# RS485_Ethernet_Gateway_v1_0.net
KiCad netlist of a schematic drawn in EAGLE
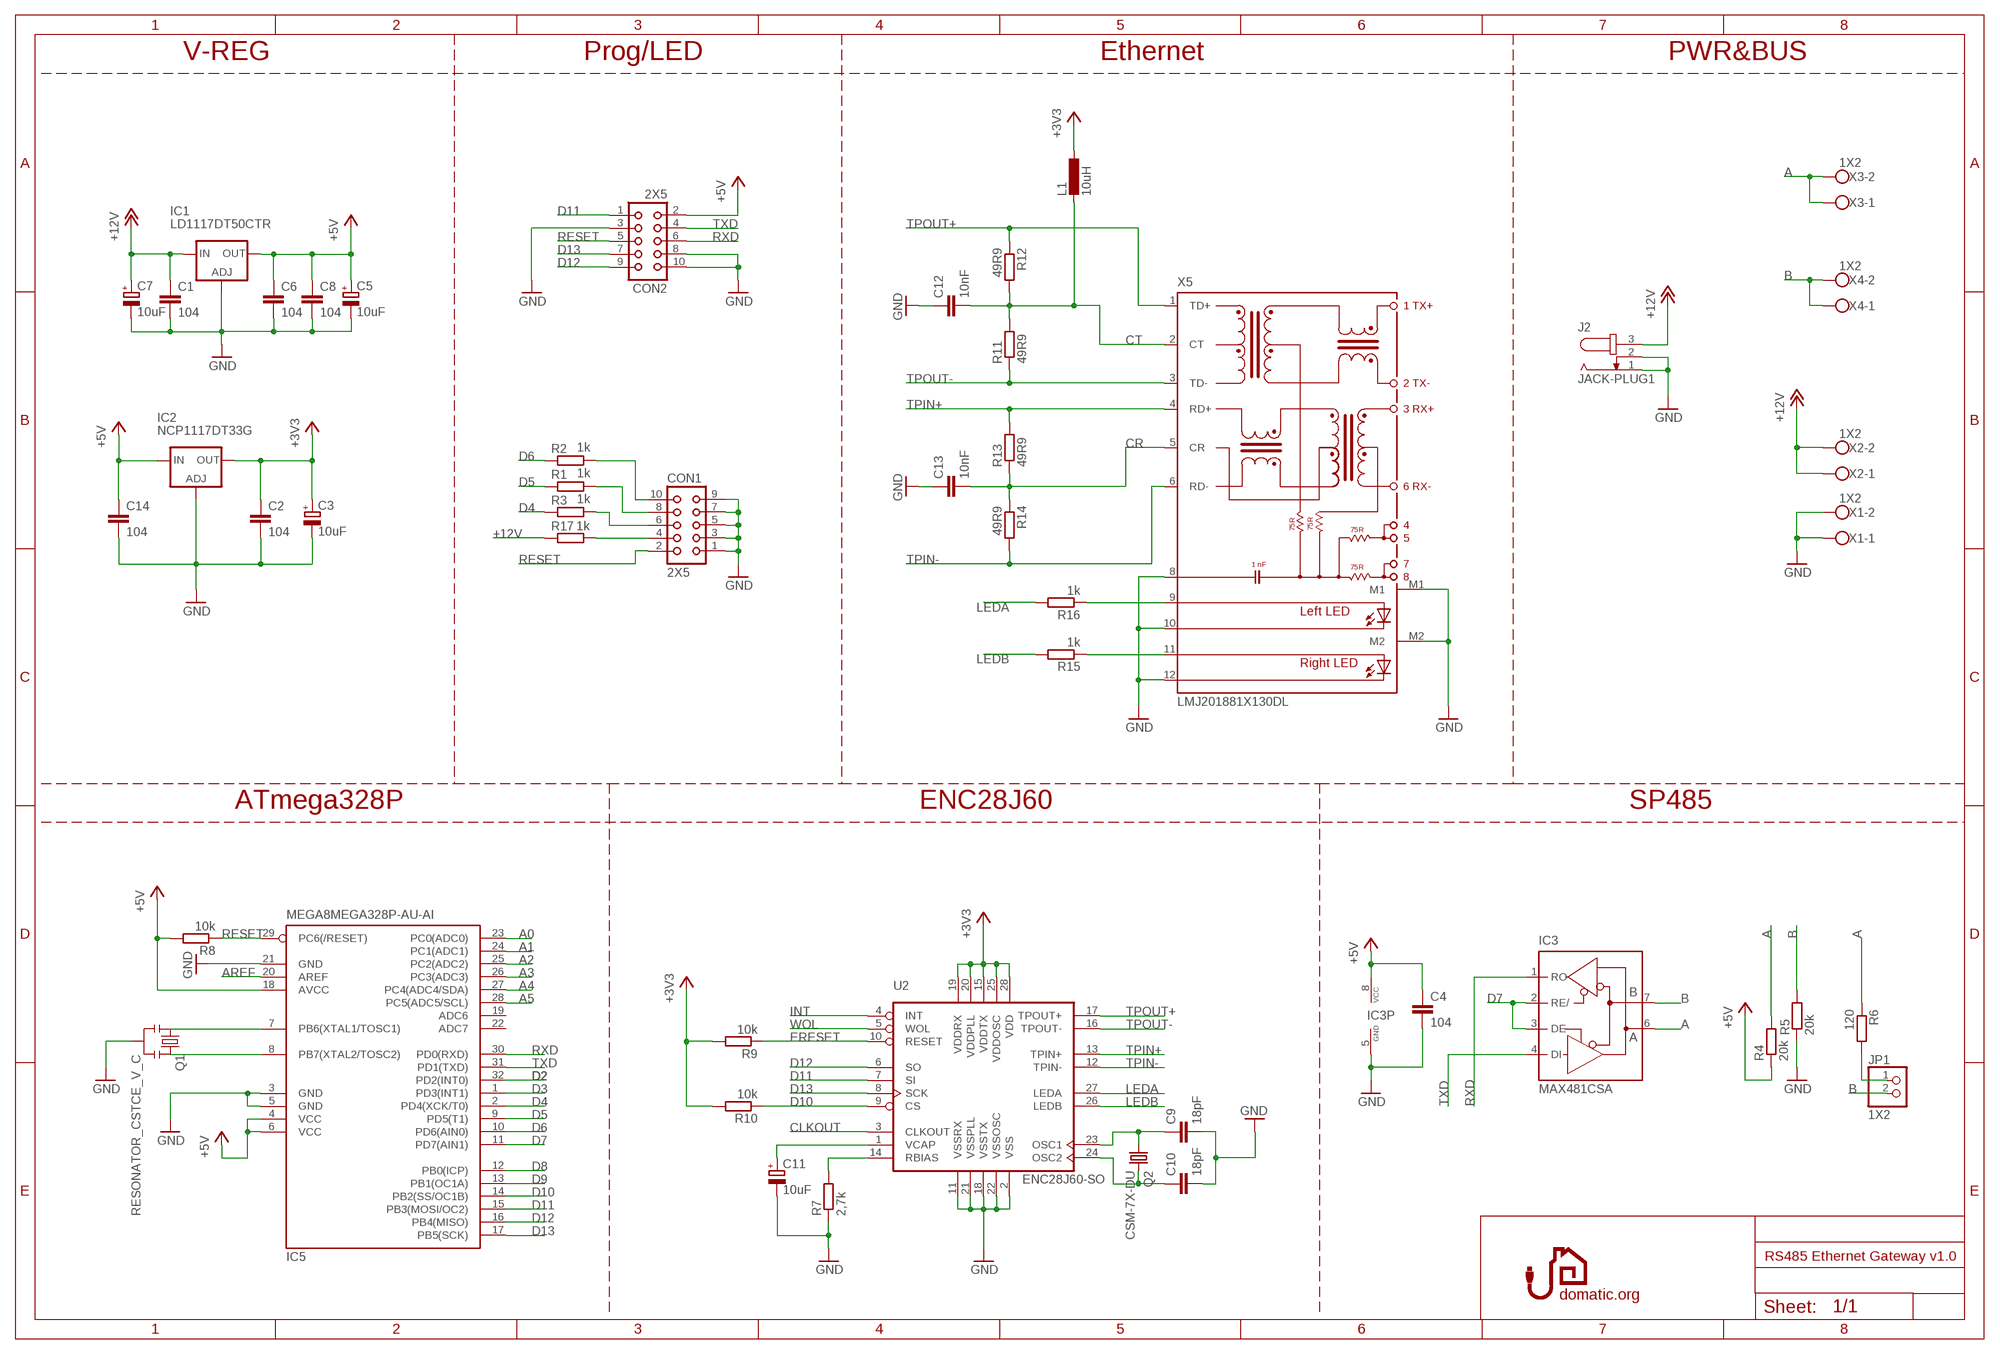
[diagram p0: schematic, sheet 1]

(export (version "E")
  (design (tool "Eeschema 10.0.6"))
  (components
    (comp (ref "C1")
      (value "104")
      (footprint "eagle-import:C0603")
      (libsource (lib "eagle-import") (part "C-EUC0603"))
    )
    (comp (ref "C2")
      (value "104")
      (footprint "eagle-import:C0603")
      (libsource (lib "eagle-import") (part "C-EUC0603"))
    )
    (comp (ref "C3")
      (value "10uF")
      (footprint "eagle-import:E2,5-7")
      (libsource (lib "eagle-import") (part "CPOL-EUE2.5-7"))
    )
    (comp (ref "C4")
      (value "104")
      (footprint "eagle-import:C0603")
      (libsource (lib "eagle-import") (part "C-EUC0603"))
    )
    (comp (ref "C5")
      (value "10uF")
      (footprint "eagle-import:E2,5-7")
      (libsource (lib "eagle-import") (part "CPOL-EUE2.5-7"))
    )
    (comp (ref "C6")
      (value "104")
      (footprint "eagle-import:C0603")
      (libsource (lib "eagle-import") (part "C-EUC0603"))
    )
    (comp (ref "C7")
      (value "10uF")
      (footprint "eagle-import:E2,5-7")
      (libsource (lib "eagle-import") (part "CPOL-EUE2.5-7"))
    )
    (comp (ref "C8")
      (value "104")
      (footprint "eagle-import:C0603")
      (libsource (lib "eagle-import") (part "C-EUC0603"))
    )
    (comp (ref "C9")
      (value "18pF")
      (footprint "eagle-import:C0603")
      (libsource (lib "eagle-import") (part "C-EUC0603"))
    )
    (comp (ref "C10")
      (value "18pF")
      (footprint "eagle-import:C0603")
      (libsource (lib "eagle-import") (part "C-EUC0603"))
    )
    (comp (ref "C11")
      (value "10uF")
      (footprint "eagle-import:E2,5-7")
      (libsource (lib "eagle-import") (part "CPOL-EUE2.5-7"))
    )
    (comp (ref "C12")
      (value "10nF")
      (footprint "eagle-import:C0603")
      (libsource (lib "eagle-import") (part "C-EUC0603"))
    )
    (comp (ref "C13")
      (value "10nF")
      (footprint "eagle-import:C0603")
      (libsource (lib "eagle-import") (part "C-EUC0603"))
    )
    (comp (ref "C14")
      (value "104")
      (footprint "eagle-import:C0603")
      (libsource (lib "eagle-import") (part "C-EUC0603"))
    )
    (comp (ref "CON1")
      (value "2X5")
      (footprint "eagle-import:CON10L")
      (libsource (lib "eagle-import") (part "CON10L"))
    )
    (comp (ref "CON2")
      (value "2X5")
      (footprint "eagle-import:CON10L")
      (libsource (lib "eagle-import") (part "CON10L"))
    )
    (comp (ref "IC1")
      (value "LD1117DT50CTR")
      (footprint "eagle-import:DPACK")
      (libsource (lib "eagle-import") (part "LD117A?DT50TR"))
    )
    (comp (ref "IC2")
      (value "NCP1117DT33G")
      (footprint "eagle-import:DPACK")
      (libsource (lib "eagle-import") (part "LD117A?DT33TR"))
    )
    (comp (ref "IC3")
      (value "MAX481CSA")
      (footprint "eagle-import:SO08")
      (fields (field (name "MF") "MAXIM"))
      (libsource (lib "eagle-import") (part "MAX481CSA"))
    )
    (comp (ref "IC5")
      (value "MEGA8MEGA328P-AU-AI")
      (footprint "eagle-import:TQFP32-08")
      (fields (field (name "MPN") "ATMEGA328P-AU"))
      (libsource (lib "eagle-import") (part "MEGA8-AIMEGA328P-AU"))
    )
    (comp (ref "J2")
      (value "JACK-PLUG1")
      (footprint "eagle-import:SPC4078")
      (libsource (lib "eagle-import") (part "JACK-PLUG1"))
    )
    (comp (ref "JP1")
      (value "1X2")
      (footprint "eagle-import:1X02")
      (libsource (lib "eagle-import") (part "PINHD-1X2"))
    )
    (comp (ref "L1")
      (value "10uH")
      (footprint "eagle-import:C1608")
      (libsource (lib "eagle-import") (part "L-EU0603"))
    )
    (comp (ref "Q1")
      (value "RESONATOR_CSTCE_V_C")
      (footprint "eagle-import:CSTCE_V_C")
      (libsource (lib "eagle-import") (part "RESONATOR_CSTCE_V_C"))
    )
    (comp (ref "Q2")
      (value "CSM-7X-DU")
      (footprint "eagle-import:CSM-7X-DU")
      (libsource (lib "eagle-import") (part "CSM-7X-DU"))
    )
    (comp (ref "R1")
      (value "1k")
      (footprint "eagle-import:R0603")
      (libsource (lib "eagle-import") (part "R-EU_R0603"))
    )
    (comp (ref "R2")
      (value "1k")
      (footprint "eagle-import:R0603")
      (libsource (lib "eagle-import") (part "R-EU_R0603"))
    )
    (comp (ref "R3")
      (value "1k")
      (footprint "eagle-import:R0603")
      (libsource (lib "eagle-import") (part "R-EU_R0603"))
    )
    (comp (ref "R4")
      (value "20k")
      (footprint "eagle-import:R0603")
      (libsource (lib "eagle-import") (part "R-EU_R0603"))
    )
    (comp (ref "R5")
      (value "20k")
      (footprint "eagle-import:R0603")
      (libsource (lib "eagle-import") (part "R-EU_R0603"))
    )
    (comp (ref "R6")
      (value "120")
      (footprint "eagle-import:R0603")
      (libsource (lib "eagle-import") (part "R-EU_R0603"))
    )
    (comp (ref "R7")
      (value "2,7k")
      (footprint "eagle-import:R0603")
      (libsource (lib "eagle-import") (part "R-EU_R0603"))
    )
    (comp (ref "R8")
      (value "10k")
      (footprint "eagle-import:R0603")
      (libsource (lib "eagle-import") (part "R-EU_R0603"))
    )
    (comp (ref "R9")
      (value "10k")
      (footprint "eagle-import:R0603")
      (libsource (lib "eagle-import") (part "R-EU_R0603"))
    )
    (comp (ref "R10")
      (value "10k")
      (footprint "eagle-import:R0603")
      (libsource (lib "eagle-import") (part "R-EU_R0603"))
    )
    (comp (ref "R11")
      (value "49R9")
      (footprint "eagle-import:R0603")
      (libsource (lib "eagle-import") (part "R-EU_R0603"))
    )
    (comp (ref "R12")
      (value "49R9")
      (footprint "eagle-import:R0603")
      (libsource (lib "eagle-import") (part "R-EU_R0603"))
    )
    (comp (ref "R13")
      (value "49R9")
      (footprint "eagle-import:R0603")
      (libsource (lib "eagle-import") (part "R-EU_R0603"))
    )
    (comp (ref "R14")
      (value "49R9")
      (footprint "eagle-import:R0603")
      (libsource (lib "eagle-import") (part "R-EU_R0603"))
    )
    (comp (ref "R15")
      (value "1k")
      (footprint "eagle-import:R0603")
      (libsource (lib "eagle-import") (part "R-EU_R0603"))
    )
    (comp (ref "R16")
      (value "1k")
      (footprint "eagle-import:R0603")
      (libsource (lib "eagle-import") (part "R-EU_R0603"))
    )
    (comp (ref "R17")
      (value "1k")
      (footprint "eagle-import:R0603")
      (libsource (lib "eagle-import") (part "R-EU_R0603"))
    )
    (comp (ref "U2")
      (value "ENC28J60-SO")
      (footprint "eagle-import:SO28W")
      (libsource (lib "eagle-import") (part "ENC28J60-SO"))
    )
    (comp (ref "X1")
      (value "1X2")
      (footprint "eagle-import:W237-102")
      (fields (field (name "MPN") "237-102"))
      (libsource (lib "eagle-import") (part "W237-102"))
    )
    (comp (ref "X2")
      (value "1X2")
      (footprint "eagle-import:W237-102")
      (fields (field (name "MPN") "237-102"))
      (libsource (lib "eagle-import") (part "W237-102"))
    )
    (comp (ref "X3")
      (value "1X2")
      (footprint "eagle-import:W237-102")
      (fields (field (name "MPN") "237-102"))
      (libsource (lib "eagle-import") (part "W237-102"))
    )
    (comp (ref "X4")
      (value "1X2")
      (footprint "eagle-import:W237-102")
      (fields (field (name "MPN") "237-102"))
      (libsource (lib "eagle-import") (part "W237-102"))
    )
    (comp (ref "X5")
      (value "LMJ201881X130DL")
      (footprint "eagle-import:LMJ20188X130")
      (libsource (lib "eagle-import") (part "LMJ201881X130DL"))
    )
  )
  (nets
    (net (code "1") (name "+3V3") (class "Default")
      (node (ref "C2") (pin "1") (pinfunction "1_1") (pintype "passive"))
      (node (ref "C3") (pin "+") (pinfunction "+_+") (pintype "passive"))
      (node (ref "IC2") (pin "4") (pinfunction "OUT_4") (pintype "passive"))
      (node (ref "L1") (pin "1") (pinfunction "1_1") (pintype "passive"))
      (node (ref "R10") (pin "2") (pinfunction "2_2") (pintype "passive"))
      (node (ref "R9") (pin "2") (pinfunction "2_2") (pintype "passive"))
      (node (ref "U2") (pin "15") (pinfunction "VDDTX_15") (pintype "power_in"))
      (node (ref "U2") (pin "19") (pinfunction "VDDRX_19") (pintype "power_in"))
      (node (ref "U2") (pin "20") (pinfunction "VDDPLL_20") (pintype "power_in"))
      (node (ref "U2") (pin "25") (pinfunction "VDDOSC_25") (pintype "power_in"))
      (node (ref "U2") (pin "28") (pinfunction "VDD_28") (pintype "power_in"))
    )
    (net (code "2") (name "+5V") (class "Default")
      (node (ref "C14") (pin "1") (pinfunction "1_1") (pintype "passive"))
      (node (ref "C4") (pin "1") (pinfunction "1_1") (pintype "passive"))
      (node (ref "C5") (pin "+") (pinfunction "+_+") (pintype "passive"))
      (node (ref "C6") (pin "1") (pinfunction "1_1") (pintype "passive"))
      (node (ref "C8") (pin "1") (pinfunction "1_1") (pintype "passive"))
      (node (ref "CON2") (pin "2") (pinfunction "2_2") (pintype "passive"))
      (node (ref "IC1") (pin "4") (pinfunction "OUT_4") (pintype "passive"))
      (node (ref "IC2") (pin "3") (pinfunction "IN_3") (pintype "input"))
      (node (ref "IC3") (pin "8") (pinfunction "VCC_8") (pintype "power_in"))
      (node (ref "IC5") (pin "18") (pinfunction "AVCC_18") (pintype "power_in"))
      (node (ref "IC5") (pin "4") (pinfunction "VCC_4") (pintype "power_in"))
      (node (ref "IC5") (pin "6") (pinfunction "VCC_6") (pintype "power_in"))
      (node (ref "R4") (pin "1") (pinfunction "1_1") (pintype "passive"))
      (node (ref "R8") (pin "2") (pinfunction "2_2") (pintype "passive"))
    )
    (net (code "3") (name "+12V") (class "Default")
      (node (ref "C1") (pin "1") (pinfunction "1_1") (pintype "passive"))
      (node (ref "C7") (pin "+") (pinfunction "+_+") (pintype "passive"))
      (node (ref "IC1") (pin "3") (pinfunction "IN_3") (pintype "input"))
      (node (ref "J2") (pin "3") (pinfunction "3_3") (pintype "passive"))
      (node (ref "R17") (pin "2") (pinfunction "2_2") (pintype "passive"))
      (node (ref "X2") (pin "1") (pinfunction "KL_1") (pintype "passive"))
      (node (ref "X2") (pin "2") (pinfunction "KL_2") (pintype "passive"))
    )
    (net (code "4") (name "/A") (class "Default")
      (node (ref "IC3") (pin "6") (pinfunction "A_6") (pintype "passive"))
      (node (ref "R4") (pin "2") (pinfunction "2_2") (pintype "passive"))
      (node (ref "R6") (pin "1") (pinfunction "1_1") (pintype "passive"))
      (node (ref "X3") (pin "1") (pinfunction "KL_1") (pintype "passive"))
      (node (ref "X3") (pin "2") (pinfunction "KL_2") (pintype "passive"))
    )
    (net (code "5") (name "/A0") (class "Default")
      (node (ref "IC5") (pin "23") (pinfunction "PC0(ADC0)_23") (pintype "bidirectional"))
    )
    (net (code "6") (name "/A1") (class "Default")
      (node (ref "IC5") (pin "24") (pinfunction "PC1(ADC1)_24") (pintype "bidirectional"))
    )
    (net (code "7") (name "/A2") (class "Default")
      (node (ref "IC5") (pin "25") (pinfunction "PC2(ADC2)_25") (pintype "bidirectional"))
    )
    (net (code "8") (name "/A3") (class "Default")
      (node (ref "IC5") (pin "26") (pinfunction "PC3(ADC3)_26") (pintype "bidirectional"))
    )
    (net (code "9") (name "/A4") (class "Default")
      (node (ref "IC5") (pin "27") (pinfunction "PC4(ADC4/SDA)_27") (pintype "bidirectional"))
    )
    (net (code "10") (name "/A5") (class "Default")
      (node (ref "IC5") (pin "28") (pinfunction "PC5(ADC5/SCL)_28") (pintype "bidirectional"))
    )
    (net (code "11") (name "/AREF") (class "Default")
      (node (ref "IC5") (pin "20") (pinfunction "AREF_20") (pintype "passive"))
    )
    (net (code "12") (name "/B") (class "Default")
      (node (ref "IC3") (pin "7") (pinfunction "B_7") (pintype "passive"))
      (node (ref "JP1") (pin "2") (pinfunction "2_2") (pintype "passive"))
      (node (ref "R5") (pin "2") (pinfunction "2_2") (pintype "passive"))
      (node (ref "X4") (pin "1") (pinfunction "KL_1") (pintype "passive"))
      (node (ref "X4") (pin "2") (pinfunction "KL_2") (pintype "passive"))
    )
    (net (code "13") (name "/CLKOUT") (class "Default")
      (node (ref "U2") (pin "3") (pinfunction "CLKOUT_3") (pintype "output"))
    )
    (net (code "14") (name "/CR") (class "Default")
      (node (ref "C13") (pin "2") (pinfunction "2_2") (pintype "passive"))
      (node (ref "R13") (pin "1") (pinfunction "1_1") (pintype "passive"))
      (node (ref "R14") (pin "1") (pinfunction "1_1") (pintype "passive"))
      (node (ref "X5") (pin "5") (pinfunction "CR_5") (pintype "input"))
    )
    (net (code "15") (name "/CT") (class "Default")
      (node (ref "C12") (pin "2") (pinfunction "2_2") (pintype "passive"))
      (node (ref "L1") (pin "2") (pinfunction "2_2") (pintype "passive"))
      (node (ref "R11") (pin "2") (pinfunction "2_2") (pintype "passive"))
      (node (ref "R12") (pin "2") (pinfunction "2_2") (pintype "passive"))
      (node (ref "X5") (pin "2") (pinfunction "CT_2") (pintype "input"))
    )
    (net (code "16") (name "/D2") (class "Default")
      (node (ref "IC5") (pin "32") (pinfunction "PD2(INT0)_32") (pintype "bidirectional"))
    )
    (net (code "17") (name "/D3") (class "Default")
      (node (ref "IC5") (pin "1") (pinfunction "PD3(INT1)_1") (pintype "bidirectional"))
    )
    (net (code "18") (name "/D4") (class "Default")
      (node (ref "IC5") (pin "2") (pinfunction "PD4(XCK/T0)_2") (pintype "bidirectional"))
      (node (ref "R3") (pin "1") (pinfunction "1_1") (pintype "passive"))
    )
    (net (code "19") (name "/D5") (class "Default")
      (node (ref "IC5") (pin "9") (pinfunction "PD5(T1)_9") (pintype "bidirectional"))
      (node (ref "R1") (pin "1") (pinfunction "1_1") (pintype "passive"))
    )
    (net (code "20") (name "/D6") (class "Default")
      (node (ref "IC5") (pin "10") (pinfunction "PD6(AIN0)_10") (pintype "bidirectional"))
      (node (ref "R2") (pin "1") (pinfunction "1_1") (pintype "passive"))
    )
    (net (code "21") (name "/D7") (class "Default")
      (node (ref "IC3") (pin "2") (pinfunction "RE/_2") (pintype "input"))
      (node (ref "IC3") (pin "3") (pinfunction "DE_3") (pintype "input"))
      (node (ref "IC5") (pin "11") (pinfunction "PD7(AIN1)_11") (pintype "bidirectional"))
    )
    (net (code "22") (name "/D8") (class "Default")
      (node (ref "IC5") (pin "12") (pinfunction "PB0(ICP)_12") (pintype "bidirectional"))
    )
    (net (code "23") (name "/D9") (class "Default")
      (node (ref "IC5") (pin "13") (pinfunction "PB1(OC1A)_13") (pintype "bidirectional"))
    )
    (net (code "24") (name "/D10") (class "Default")
      (node (ref "IC5") (pin "14") (pinfunction "PB2(SS/OC1B)_14") (pintype "bidirectional"))
      (node (ref "R10") (pin "1") (pinfunction "1_1") (pintype "passive"))
      (node (ref "U2") (pin "9") (pinfunction "CS_9") (pintype "input"))
    )
    (net (code "25") (name "/D11") (class "Default")
      (node (ref "CON2") (pin "1") (pinfunction "1_1") (pintype "passive"))
      (node (ref "IC5") (pin "15") (pinfunction "PB3(MOSI/OC2)_15") (pintype "bidirectional"))
      (node (ref "U2") (pin "7") (pinfunction "SI_7") (pintype "input"))
    )
    (net (code "26") (name "/D12") (class "Default")
      (node (ref "CON2") (pin "9") (pinfunction "9_9") (pintype "passive"))
      (node (ref "IC5") (pin "16") (pinfunction "PB4(MISO)_16") (pintype "bidirectional"))
      (node (ref "U2") (pin "6") (pinfunction "SO_6") (pintype "output"))
    )
    (net (code "27") (name "/D13") (class "Default")
      (node (ref "CON2") (pin "7") (pinfunction "7_7") (pintype "passive"))
      (node (ref "IC5") (pin "17") (pinfunction "PB5(SCK)_17") (pintype "bidirectional"))
      (node (ref "U2") (pin "8") (pinfunction "SCK_8") (pintype "input"))
    )
    (net (code "28") (name "/ERESET") (class "Default")
      (node (ref "R9") (pin "1") (pinfunction "1_1") (pintype "passive"))
      (node (ref "U2") (pin "10") (pinfunction "RESET_10") (pintype "input"))
    )
    (net (code "29") (name "/INT") (class "Default")
      (node (ref "U2") (pin "4") (pinfunction "INT_4") (pintype "output"))
    )
    (net (code "30") (name "/LEDA") (class "Default")
      (node (ref "R16") (pin "2") (pinfunction "2_2") (pintype "passive"))
      (node (ref "U2") (pin "27") (pinfunction "LEDA_27") (pintype "output"))
    )
    (net (code "31") (name "/LEDB") (class "Default")
      (node (ref "R15") (pin "2") (pinfunction "2_2") (pintype "passive"))
      (node (ref "U2") (pin "26") (pinfunction "LEDB_26") (pintype "output"))
    )
    (net (code "32") (name "/RESET") (class "Default")
      (node (ref "CON1") (pin "2") (pinfunction "2_2") (pintype "passive"))
      (node (ref "CON2") (pin "5") (pinfunction "5_5") (pintype "passive"))
      (node (ref "IC5") (pin "29") (pinfunction "PC6(/RESET)_29") (pintype "bidirectional"))
      (node (ref "R8") (pin "1") (pinfunction "1_1") (pintype "passive"))
    )
    (net (code "33") (name "/RXD") (class "Default")
      (node (ref "CON2") (pin "6") (pinfunction "6_6") (pintype "passive"))
      (node (ref "IC3") (pin "1") (pinfunction "RO_1") (pintype "output"))
      (node (ref "IC5") (pin "30") (pinfunction "PD0(RXD)_30") (pintype "bidirectional"))
    )
    (net (code "34") (name "/TPIN+") (class "Default")
      (node (ref "R13") (pin "2") (pinfunction "2_2") (pintype "passive"))
      (node (ref "U2") (pin "13") (pinfunction "TPIN+_13") (pintype "input"))
      (node (ref "X5") (pin "4") (pinfunction "RD+_4") (pintype "input"))
    )
    (net (code "35") (name "/TPIN-") (class "Default")
      (node (ref "R14") (pin "2") (pinfunction "2_2") (pintype "passive"))
      (node (ref "U2") (pin "12") (pinfunction "TPIN-_12") (pintype "input"))
      (node (ref "X5") (pin "6") (pinfunction "RD-_6") (pintype "input"))
    )
    (net (code "36") (name "/TPOUT+") (class "Default")
      (node (ref "R12") (pin "1") (pinfunction "1_1") (pintype "passive"))
      (node (ref "U2") (pin "17") (pinfunction "TPOUT+_17") (pintype "output"))
      (node (ref "X5") (pin "1") (pinfunction "TD+_1") (pintype "input"))
    )
    (net (code "37") (name "/TPOUT-") (class "Default")
      (node (ref "R11") (pin "1") (pinfunction "1_1") (pintype "passive"))
      (node (ref "U2") (pin "16") (pinfunction "TPOUT-_16") (pintype "output"))
      (node (ref "X5") (pin "3") (pinfunction "TD-_3") (pintype "input"))
    )
    (net (code "38") (name "/TXD") (class "Default")
      (node (ref "CON2") (pin "4") (pinfunction "4_4") (pintype "passive"))
      (node (ref "IC3") (pin "4") (pinfunction "DI_4") (pintype "input"))
      (node (ref "IC5") (pin "31") (pinfunction "PD1(TXD)_31") (pintype "bidirectional"))
    )
    (net (code "39") (name "/WOL") (class "Default")
      (node (ref "U2") (pin "5") (pinfunction "WOL_5") (pintype "output"))
    )
    (net (code "40") (name "GND") (class "Default")
      (node (ref "C1") (pin "2") (pinfunction "2_2") (pintype "passive"))
      (node (ref "C10") (pin "2") (pinfunction "2_2") (pintype "passive"))
      (node (ref "C11") (pin "-") (pinfunction "-_-") (pintype "passive"))
      (node (ref "C12") (pin "1") (pinfunction "1_1") (pintype "passive"))
      (node (ref "C13") (pin "1") (pinfunction "1_1") (pintype "passive"))
      (node (ref "C14") (pin "2") (pinfunction "2_2") (pintype "passive"))
      (node (ref "C2") (pin "2") (pinfunction "2_2") (pintype "passive"))
      (node (ref "C3") (pin "-") (pinfunction "-_-") (pintype "passive"))
      (node (ref "C4") (pin "2") (pinfunction "2_2") (pintype "passive"))
      (node (ref "C5") (pin "-") (pinfunction "-_-") (pintype "passive"))
      (node (ref "C6") (pin "2") (pinfunction "2_2") (pintype "passive"))
      (node (ref "C7") (pin "-") (pinfunction "-_-") (pintype "passive"))
      (node (ref "C8") (pin "2") (pinfunction "2_2") (pintype "passive"))
      (node (ref "C9") (pin "2") (pinfunction "2_2") (pintype "passive"))
      (node (ref "CON1") (pin "1") (pinfunction "1_1") (pintype "passive"))
      (node (ref "CON1") (pin "3") (pinfunction "3_3") (pintype "passive"))
      (node (ref "CON1") (pin "5") (pinfunction "5_5") (pintype "passive"))
      (node (ref "CON1") (pin "7") (pinfunction "7_7") (pintype "passive"))
      (node (ref "CON1") (pin "9") (pinfunction "9_9") (pintype "passive"))
      (node (ref "CON2") (pin "10") (pinfunction "10_10") (pintype "passive"))
      (node (ref "CON2") (pin "3") (pinfunction "3_3") (pintype "passive"))
      (node (ref "CON2") (pin "8") (pinfunction "8_8") (pintype "passive"))
      (node (ref "IC1") (pin "1") (pinfunction "ADJ_1") (pintype "input"))
      (node (ref "IC2") (pin "1") (pinfunction "ADJ_1") (pintype "input"))
      (node (ref "IC3") (pin "5") (pinfunction "GND_5") (pintype "power_in"))
      (node (ref "IC5") (pin "21") (pinfunction "GND_21") (pintype "power_in"))
      (node (ref "IC5") (pin "3") (pinfunction "GND_3") (pintype "power_in"))
      (node (ref "IC5") (pin "5") (pinfunction "GND_5") (pintype "power_in"))
      (node (ref "J2") (pin "1") (pinfunction "1_1") (pintype "passive"))
      (node (ref "J2") (pin "2") (pinfunction "2_2") (pintype "passive"))
      (node (ref "Q1") (pin "GND") (pinfunction "GND_GND") (pintype "passive"))
      (node (ref "R5") (pin "1") (pinfunction "1_1") (pintype "passive"))
      (node (ref "R7") (pin "1") (pinfunction "1_1") (pintype "passive"))
      (node (ref "U2") (pin "11") (pinfunction "VSSRX_11") (pintype "power_in"))
      (node (ref "U2") (pin "18") (pinfunction "VSSTX_18") (pintype "power_in"))
      (node (ref "U2") (pin "2") (pinfunction "VSS_2") (pintype "power_in"))
      (node (ref "U2") (pin "21") (pinfunction "VSSPLL_21") (pintype "power_in"))
      (node (ref "U2") (pin "22") (pinfunction "VSSOSC_22") (pintype "power_in"))
      (node (ref "X1") (pin "1") (pinfunction "KL_1") (pintype "passive"))
      (node (ref "X1") (pin "2") (pinfunction "KL_2") (pintype "passive"))
      (node (ref "X5") (pin "10") (pinfunction "10_10") (pintype "passive"))
      (node (ref "X5") (pin "12") (pinfunction "12_12") (pintype "passive"))
      (node (ref "X5") (pin "8") (pinfunction "8_8") (pintype "input"))
      (node (ref "X5") (pin "M1") (pinfunction "M1_M1") (pintype "power_in"))
      (node (ref "X5") (pin "M2") (pinfunction "M2_M2") (pintype "power_in"))
    )
    (net (code "41") (name "Net-(CON1-Pad4)") (class "Default")
      (node (ref "CON1") (pin "4") (pinfunction "4_4") (pintype "passive"))
      (node (ref "R17") (pin "1") (pinfunction "1_1") (pintype "passive"))
    )
    (net (code "42") (name "Net-(CON1-Pad6)") (class "Default")
      (node (ref "CON1") (pin "6") (pinfunction "6_6") (pintype "passive"))
      (node (ref "R3") (pin "2") (pinfunction "2_2") (pintype "passive"))
    )
    (net (code "43") (name "Net-(CON1-Pad8)") (class "Default")
      (node (ref "CON1") (pin "8") (pinfunction "8_8") (pintype "passive"))
      (node (ref "R1") (pin "2") (pinfunction "2_2") (pintype "passive"))
    )
    (net (code "44") (name "Net-(CON1-Pad10)") (class "Default")
      (node (ref "CON1") (pin "10") (pinfunction "10_10") (pintype "passive"))
      (node (ref "R2") (pin "2") (pinfunction "2_2") (pintype "passive"))
    )
    (net (code "45") (name "Net-(IC5-PB6(XTAL1{slash}TOSC1))") (class "Default")
      (node (ref "IC5") (pin "7") (pinfunction "PB6(XTAL1/TOSC1)_7") (pintype "bidirectional"))
      (node (ref "Q1") (pin "X1") (pinfunction "X1_X1") (pintype "passive"))
    )
    (net (code "46") (name "Net-(IC5-PB7(XTAL2{slash}TOSC2))") (class "Default")
      (node (ref "IC5") (pin "8") (pinfunction "PB7(XTAL2/TOSC2)_8") (pintype "bidirectional"))
      (node (ref "Q1") (pin "X2") (pinfunction "X2_X2") (pintype "passive"))
    )
    (net (code "47") (name "Net-(JP1-Pad1)") (class "Default")
      (node (ref "JP1") (pin "1") (pinfunction "1_1") (pintype "passive"))
      (node (ref "R6") (pin "2") (pinfunction "2_2") (pintype "passive"))
    )
    (net (code "48") (name "Net-(R15-Pad1)") (class "Default")
      (node (ref "R15") (pin "1") (pinfunction "1_1") (pintype "passive"))
      (node (ref "X5") (pin "11") (pinfunction "11_11") (pintype "passive"))
    )
    (net (code "49") (name "Net-(R16-Pad1)") (class "Default")
      (node (ref "R16") (pin "1") (pinfunction "1_1") (pintype "passive"))
      (node (ref "X5") (pin "9") (pinfunction "9_9") (pintype "passive"))
    )
    (net (code "50") (name "Net-(U2-OSC1)") (class "Default")
      (node (ref "C9") (pin "1") (pinfunction "1_1") (pintype "passive"))
      (node (ref "Q2") (pin "1") (pinfunction "1_1") (pintype "passive"))
      (node (ref "U2") (pin "23") (pinfunction "OSC1_23") (pintype "input"))
    )
    (net (code "51") (name "Net-(U2-OSC2)") (class "Default")
      (node (ref "C10") (pin "1") (pinfunction "1_1") (pintype "passive"))
      (node (ref "Q2") (pin "2") (pinfunction "2_2") (pintype "passive"))
      (node (ref "U2") (pin "24") (pinfunction "OSC2_24") (pintype "output"))
    )
    (net (code "52") (name "Net-(U2-RBIAS)") (class "Default")
      (node (ref "R7") (pin "2") (pinfunction "2_2") (pintype "passive"))
      (node (ref "U2") (pin "14") (pinfunction "RBIAS_14") (pintype "passive"))
    )
    (net (code "53") (name "Net-(U2-VCAP)") (class "Default")
      (node (ref "C11") (pin "+") (pinfunction "+_+") (pintype "passive"))
      (node (ref "U2") (pin "1") (pinfunction "VCAP_1") (pintype "power_in"))
    )
    (net (code "54") (name "unconnected-(IC5-ADC6-Pad19)") (class "Default")
      (node (ref "IC5") (pin "19") (pinfunction "ADC6_19") (pintype "bidirectional"))
    )
    (net (code "55") (name "unconnected-(IC5-ADC7-Pad22)") (class "Default")
      (node (ref "IC5") (pin "22") (pinfunction "ADC7_22") (pintype "bidirectional"))
    )
  )
)
